# untitled.net
KiCad netlist of a schematic drawn in EAGLE
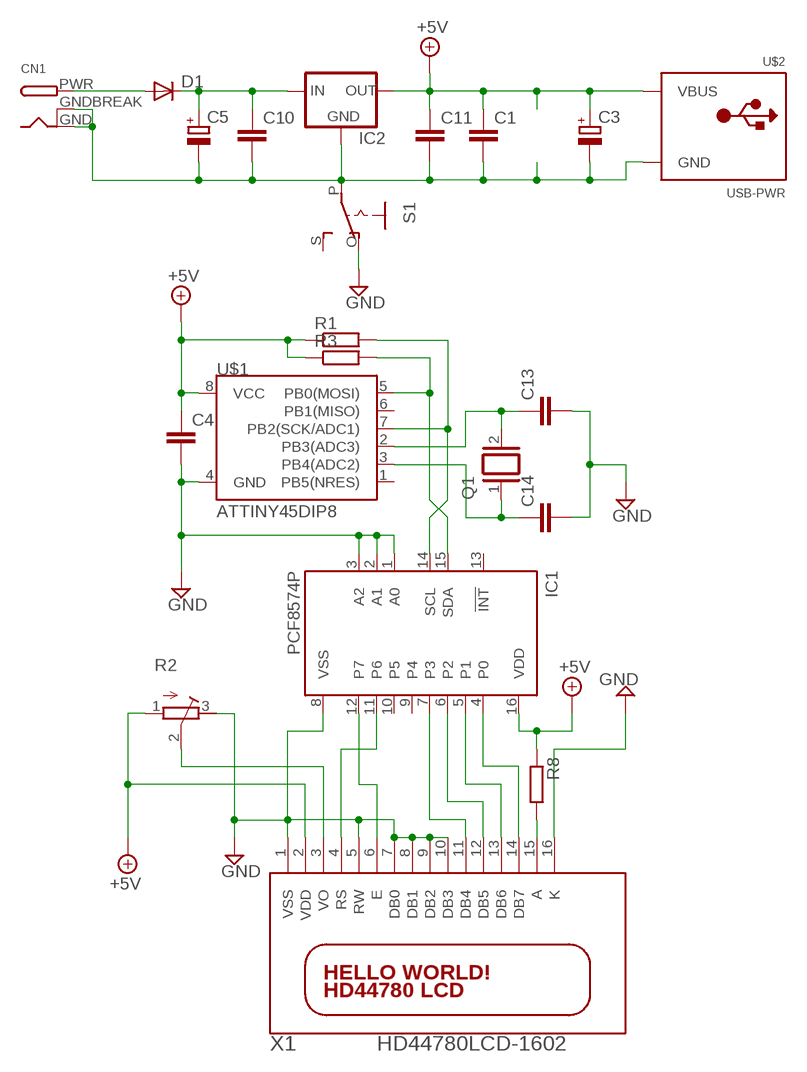
[diagram p0: schematic, sheet 1]

(export (version "E")
  (design (tool "Eeschema 10.0.6"))
  (components
    (comp (ref "C1")
      (value "C-EU025-025X050")
      (footprint "eagle-import:C025-025X050")
      (libsource (lib "eagle-import") (part "C-EU025-025X050"))
    )
    (comp (ref "C3")
      (value "CPOL-EUE2.5-6")
      (footprint "eagle-import:E2,5-6")
      (libsource (lib "eagle-import") (part "CPOL-EUE2.5-6"))
    )
    (comp (ref "C4")
      (value "C-EU025-025X050")
      (footprint "eagle-import:C025-025X050")
      (libsource (lib "eagle-import") (part "C-EU025-025X050"))
    )
    (comp (ref "C5")
      (value "CPOL-EUE2.5-6")
      (footprint "eagle-import:E2,5-6")
      (libsource (lib "eagle-import") (part "CPOL-EUE2.5-6"))
    )
    (comp (ref "C10")
      (value "C-EU025-025X050")
      (footprint "eagle-import:C025-025X050")
      (libsource (lib "eagle-import") (part "C-EU025-025X050"))
    )
    (comp (ref "C11")
      (value "C-EU025-025X050")
      (footprint "eagle-import:C025-025X050")
      (libsource (lib "eagle-import") (part "C-EU025-025X050"))
    )
    (comp (ref "C13")
      (value "C-EU025-025X050")
      (footprint "eagle-import:C025-025X050")
      (libsource (lib "eagle-import") (part "C-EU025-025X050"))
    )
    (comp (ref "C14")
      (value "C-EU025-025X050")
      (footprint "eagle-import:C025-025X050")
      (libsource (lib "eagle-import") (part "C-EU025-025X050"))
    )
    (comp (ref "CN1")
      (value "DCBARRELPTH")
      (footprint "eagle-import:DCJACK_2MM_PTH")
      (libsource (lib "eagle-import") (part "DCBARRELPTH"))
    )
    (comp (ref "D1")
      (value "DIODE-D-2.5")
      (footprint "eagle-import:D-2.5")
      (libsource (lib "eagle-import") (part "DIODE-D-2.5"))
    )
    (comp (ref "IC1")
      (value "PCF8574P")
      (footprint "eagle-import:DIL16")
      (fields (field (name "MPN") "PCF8574PN"))
      (libsource (lib "eagle-import") (part "PCF8574P"))
    )
    (comp (ref "IC2")
      (value "V_REG_78XXSIDE")
      (footprint "eagle-import:78XXL")
      (libsource (lib "eagle-import") (part "V_REG_78XXSIDE"))
    )
    (comp (ref "Q1")
      (value "XTAL/S")
      (footprint "eagle-import:QS")
      (libsource (lib "eagle-import") (part "XTAL/S"))
    )
    (comp (ref "R1")
      (value "R-EU_0207/2V")
      (footprint "eagle-import:0207_2V")
      (libsource (lib "eagle-import") (part "R-EU_0207/2V"))
    )
    (comp (ref "R2")
      (value "R-TRIMM3339P")
      (footprint "eagle-import:RTRIM3339P")
      (libsource (lib "eagle-import") (part "R-TRIMM3339P"))
    )
    (comp (ref "R3")
      (value "R-EU_0207/5V")
      (footprint "eagle-import:0207_5V")
      (libsource (lib "eagle-import") (part "R-EU_0207/5V"))
    )
    (comp (ref "R8")
      (value "R-EU_0207/10")
      (footprint "eagle-import:0207_10")
      (libsource (lib "eagle-import") (part "R-EU_0207/10"))
    )
    (comp (ref "S1")
      (value "EG1218S")
      (footprint "eagle-import:EG1218")
      (libsource (lib "eagle-import") (part "EG1218S"))
    )
    (comp (ref "U$1")
      (value "ATTINY45DIP8")
      (footprint "eagle-import:DIP08")
      (libsource (lib "eagle-import") (part "ATTINY45DIP8"))
    )
    (comp (ref "U$2")
      (value "USB-PWR")
      (footprint "eagle-import:USB-MINIB-THM-MOLEX-PWRONLY")
      (libsource (lib "eagle-import") (part "USB-PWR"))
    )
    (comp (ref "X1")
      (value "HD44780LCD-1602")
      (footprint "eagle-import:LCD1602")
      (libsource (lib "eagle-import") (part "HD44780LCD-1602"))
    )
  )
  (nets
    (net (code "1") (name "+5V") (class "Default")
      (node (ref "C1") (pin "1") (pinfunction "1_1") (pintype "passive"))
      (node (ref "C11") (pin "1") (pinfunction "1_1") (pintype "passive"))
      (node (ref "C3") (pin "+") (pinfunction "+_+") (pintype "passive"))
      (node (ref "C4") (pin "1") (pinfunction "1_1") (pintype "passive"))
      (node (ref "IC1") (pin "16") (pinfunction "VDD_16") (pintype "power_in"))
      (node (ref "IC2") (pin "OUT") (pinfunction "OUT_OUT") (pintype "output"))
      (node (ref "R1") (pin "1") (pinfunction "1_1") (pintype "passive"))
      (node (ref "R2") (pin "1") (pinfunction "A_1") (pintype "passive"))
      (node (ref "R3") (pin "1") (pinfunction "1_1") (pintype "passive"))
      (node (ref "R8") (pin "1") (pinfunction "1_1") (pintype "passive"))
      (node (ref "U$1") (pin "8") (pinfunction "VCC_8") (pintype "bidirectional"))
      (node (ref "U$2") (pin "VBUS") (pinfunction "VBUS_VBUS") (pintype "power_in"))
      (node (ref "X1") (pin "2") (pinfunction "VDD_2") (pintype "power_in"))
    )
    (net (code "2") (name "GND") (class "Default")
      (node (ref "C13") (pin "2") (pinfunction "2_2") (pintype "passive"))
      (node (ref "C14") (pin "2") (pinfunction "2_2") (pintype "passive"))
      (node (ref "C4") (pin "2") (pinfunction "2_2") (pintype "passive"))
      (node (ref "IC1") (pin "1") (pinfunction "A0_1") (pintype "input"))
      (node (ref "IC1") (pin "2") (pinfunction "A1_2") (pintype "input"))
      (node (ref "IC1") (pin "3") (pinfunction "A2_3") (pintype "input"))
      (node (ref "IC1") (pin "8") (pinfunction "VSS_8") (pintype "power_in"))
      (node (ref "R2") (pin "3") (pinfunction "E_3") (pintype "passive"))
      (node (ref "S1") (pin "O") (pinfunction "O_O") (pintype "passive"))
      (node (ref "U$1") (pin "4") (pinfunction "GND_4") (pintype "bidirectional"))
      (node (ref "X1") (pin "1") (pinfunction "VSS_1") (pintype "power_in"))
      (node (ref "X1") (pin "10") (pinfunction "DB3_10") (pintype "bidirectional"))
      (node (ref "X1") (pin "16") (pinfunction "K_16") (pintype "input"))
      (node (ref "X1") (pin "5") (pinfunction "RW_5") (pintype "input"))
      (node (ref "X1") (pin "7") (pinfunction "DB0_7") (pintype "bidirectional"))
      (node (ref "X1") (pin "8") (pinfunction "DB1_8") (pintype "bidirectional"))
      (node (ref "X1") (pin "9") (pinfunction "DB2_9") (pintype "bidirectional"))
    )
    (net (code "3") (name "Net-(C1-Pad2)") (class "Default")
      (node (ref "C1") (pin "2") (pinfunction "2_2") (pintype "passive"))
      (node (ref "C10") (pin "2") (pinfunction "2_2") (pintype "passive"))
      (node (ref "C11") (pin "2") (pinfunction "2_2") (pintype "passive"))
      (node (ref "C3") (pin "-") (pinfunction "-_-") (pintype "passive"))
      (node (ref "C5") (pin "-") (pinfunction "-_-") (pintype "passive"))
      (node (ref "CN1") (pin "GND") (pinfunction "GND_GND") (pintype "power_in"))
      (node (ref "CN1") (pin "GNDBREAK") (pinfunction "GNDBREAK_GNDBREAK") (pintype "power_in"))
      (node (ref "IC2") (pin "GND") (pinfunction "GND_GND") (pintype "input"))
      (node (ref "S1") (pin "P") (pinfunction "P_P") (pintype "passive"))
      (node (ref "U$2") (pin "GND") (pinfunction "GND_GND") (pintype "power_in"))
    )
    (net (code "4") (name "Net-(C10-Pad1)") (class "Default")
      (node (ref "C10") (pin "1") (pinfunction "1_1") (pintype "passive"))
      (node (ref "C5") (pin "+") (pinfunction "+_+") (pintype "passive"))
      (node (ref "D1") (pin "C") (pinfunction "C_C") (pintype "passive"))
      (node (ref "IC2") (pin "IN") (pinfunction "IN_IN") (pintype "input"))
    )
    (net (code "5") (name "Net-(CN1-PadPWR)") (class "Default")
      (node (ref "CN1") (pin "PWR") (pinfunction "PWR_PWR") (pintype "power_in"))
      (node (ref "D1") (pin "A") (pinfunction "A_A") (pintype "passive"))
    )
    (net (code "6") (name "Net-(IC1-P0)") (class "Default")
      (node (ref "IC1") (pin "4") (pinfunction "P0_4") (pintype "bidirectional"))
      (node (ref "X1") (pin "14") (pinfunction "DB7_14") (pintype "bidirectional"))
    )
    (net (code "7") (name "Net-(IC1-P1)") (class "Default")
      (node (ref "IC1") (pin "5") (pinfunction "P1_5") (pintype "bidirectional"))
      (node (ref "X1") (pin "13") (pinfunction "DB6_13") (pintype "bidirectional"))
    )
    (net (code "8") (name "Net-(IC1-P2)") (class "Default")
      (node (ref "IC1") (pin "6") (pinfunction "P2_6") (pintype "bidirectional"))
      (node (ref "X1") (pin "12") (pinfunction "DB5_12") (pintype "bidirectional"))
    )
    (net (code "9") (name "Net-(IC1-P3)") (class "Default")
      (node (ref "IC1") (pin "7") (pinfunction "P3_7") (pintype "bidirectional"))
      (node (ref "X1") (pin "11") (pinfunction "DB4_11") (pintype "bidirectional"))
    )
    (net (code "10") (name "Net-(IC1-P6)") (class "Default")
      (node (ref "IC1") (pin "11") (pinfunction "P6_11") (pintype "bidirectional"))
      (node (ref "X1") (pin "4") (pinfunction "RS_4") (pintype "input"))
    )
    (net (code "11") (name "Net-(IC1-P7)") (class "Default")
      (node (ref "IC1") (pin "12") (pinfunction "P7_12") (pintype "bidirectional"))
      (node (ref "X1") (pin "6") (pinfunction "E_6") (pintype "input"))
    )
    (net (code "12") (name "Net-(IC1-SCL)") (class "Default")
      (node (ref "IC1") (pin "14") (pinfunction "SCL_14") (pintype "input"))
      (node (ref "R1") (pin "2") (pinfunction "2_2") (pintype "passive"))
      (node (ref "U$1") (pin "7") (pinfunction "PB2(SCK/ADC1)_7") (pintype "bidirectional"))
    )
    (net (code "13") (name "Net-(IC1-SDA)") (class "Default")
      (node (ref "IC1") (pin "15") (pinfunction "SDA_15") (pintype "bidirectional"))
      (node (ref "R3") (pin "2") (pinfunction "2_2") (pintype "passive"))
      (node (ref "U$1") (pin "5") (pinfunction "PB0(MOSI)_5") (pintype "bidirectional"))
    )
    (net (code "14") (name "Net-(R2-S)") (class "Default")
      (node (ref "R2") (pin "2") (pinfunction "S_2") (pintype "passive"))
      (node (ref "X1") (pin "3") (pinfunction "VO_3") (pintype "input"))
    )
    (net (code "15") (name "Net-(U$1-PB3(ADC3))") (class "Default")
      (node (ref "C13") (pin "1") (pinfunction "1_1") (pintype "passive"))
      (node (ref "Q1") (pin "2") (pinfunction "2_2") (pintype "passive"))
      (node (ref "U$1") (pin "2") (pinfunction "PB3(ADC3)_2") (pintype "bidirectional"))
    )
    (net (code "16") (name "Net-(U$1-PB4(ADC2))") (class "Default")
      (node (ref "C14") (pin "1") (pinfunction "1_1") (pintype "passive"))
      (node (ref "Q1") (pin "1") (pinfunction "1_1") (pintype "passive"))
      (node (ref "U$1") (pin "3") (pinfunction "PB4(ADC2)_3") (pintype "bidirectional"))
    )
    (net (code "17") (name "Net-(X1-A)") (class "Default")
      (node (ref "R8") (pin "2") (pinfunction "2_2") (pintype "passive"))
      (node (ref "X1") (pin "15") (pinfunction "A_15") (pintype "input"))
    )
    (net (code "18") (name "unconnected-(IC1-P4-Pad9)") (class "Default")
      (node (ref "IC1") (pin "9") (pinfunction "P4_9") (pintype "bidirectional"))
    )
    (net (code "19") (name "unconnected-(IC1-P5-Pad10)") (class "Default")
      (node (ref "IC1") (pin "10") (pinfunction "P5_10") (pintype "bidirectional"))
    )
    (net (code "20") (name "unconnected-(IC1-~{INT}-Pad13)") (class "Default")
      (node (ref "IC1") (pin "13") (pinfunction "~{INT}_13") (pintype "output"))
    )
    (net (code "21") (name "unconnected-(S1-PadS)") (class "Default")
      (node (ref "S1") (pin "S") (pinfunction "S_S") (pintype "passive"))
    )
    (net (code "22") (name "unconnected-(U$1-PB1(MISO)-Pad6)") (class "Default")
      (node (ref "U$1") (pin "6") (pinfunction "PB1(MISO)_6") (pintype "bidirectional"))
    )
    (net (code "23") (name "unconnected-(U$1-PB5(NRES)-Pad1)") (class "Default")
      (node (ref "U$1") (pin "1") (pinfunction "PB5(NRES)_1") (pintype "bidirectional"))
    )
  )
)
